# PCB.net
KiCad netlist of a schematic drawn in EasyEDA Pro
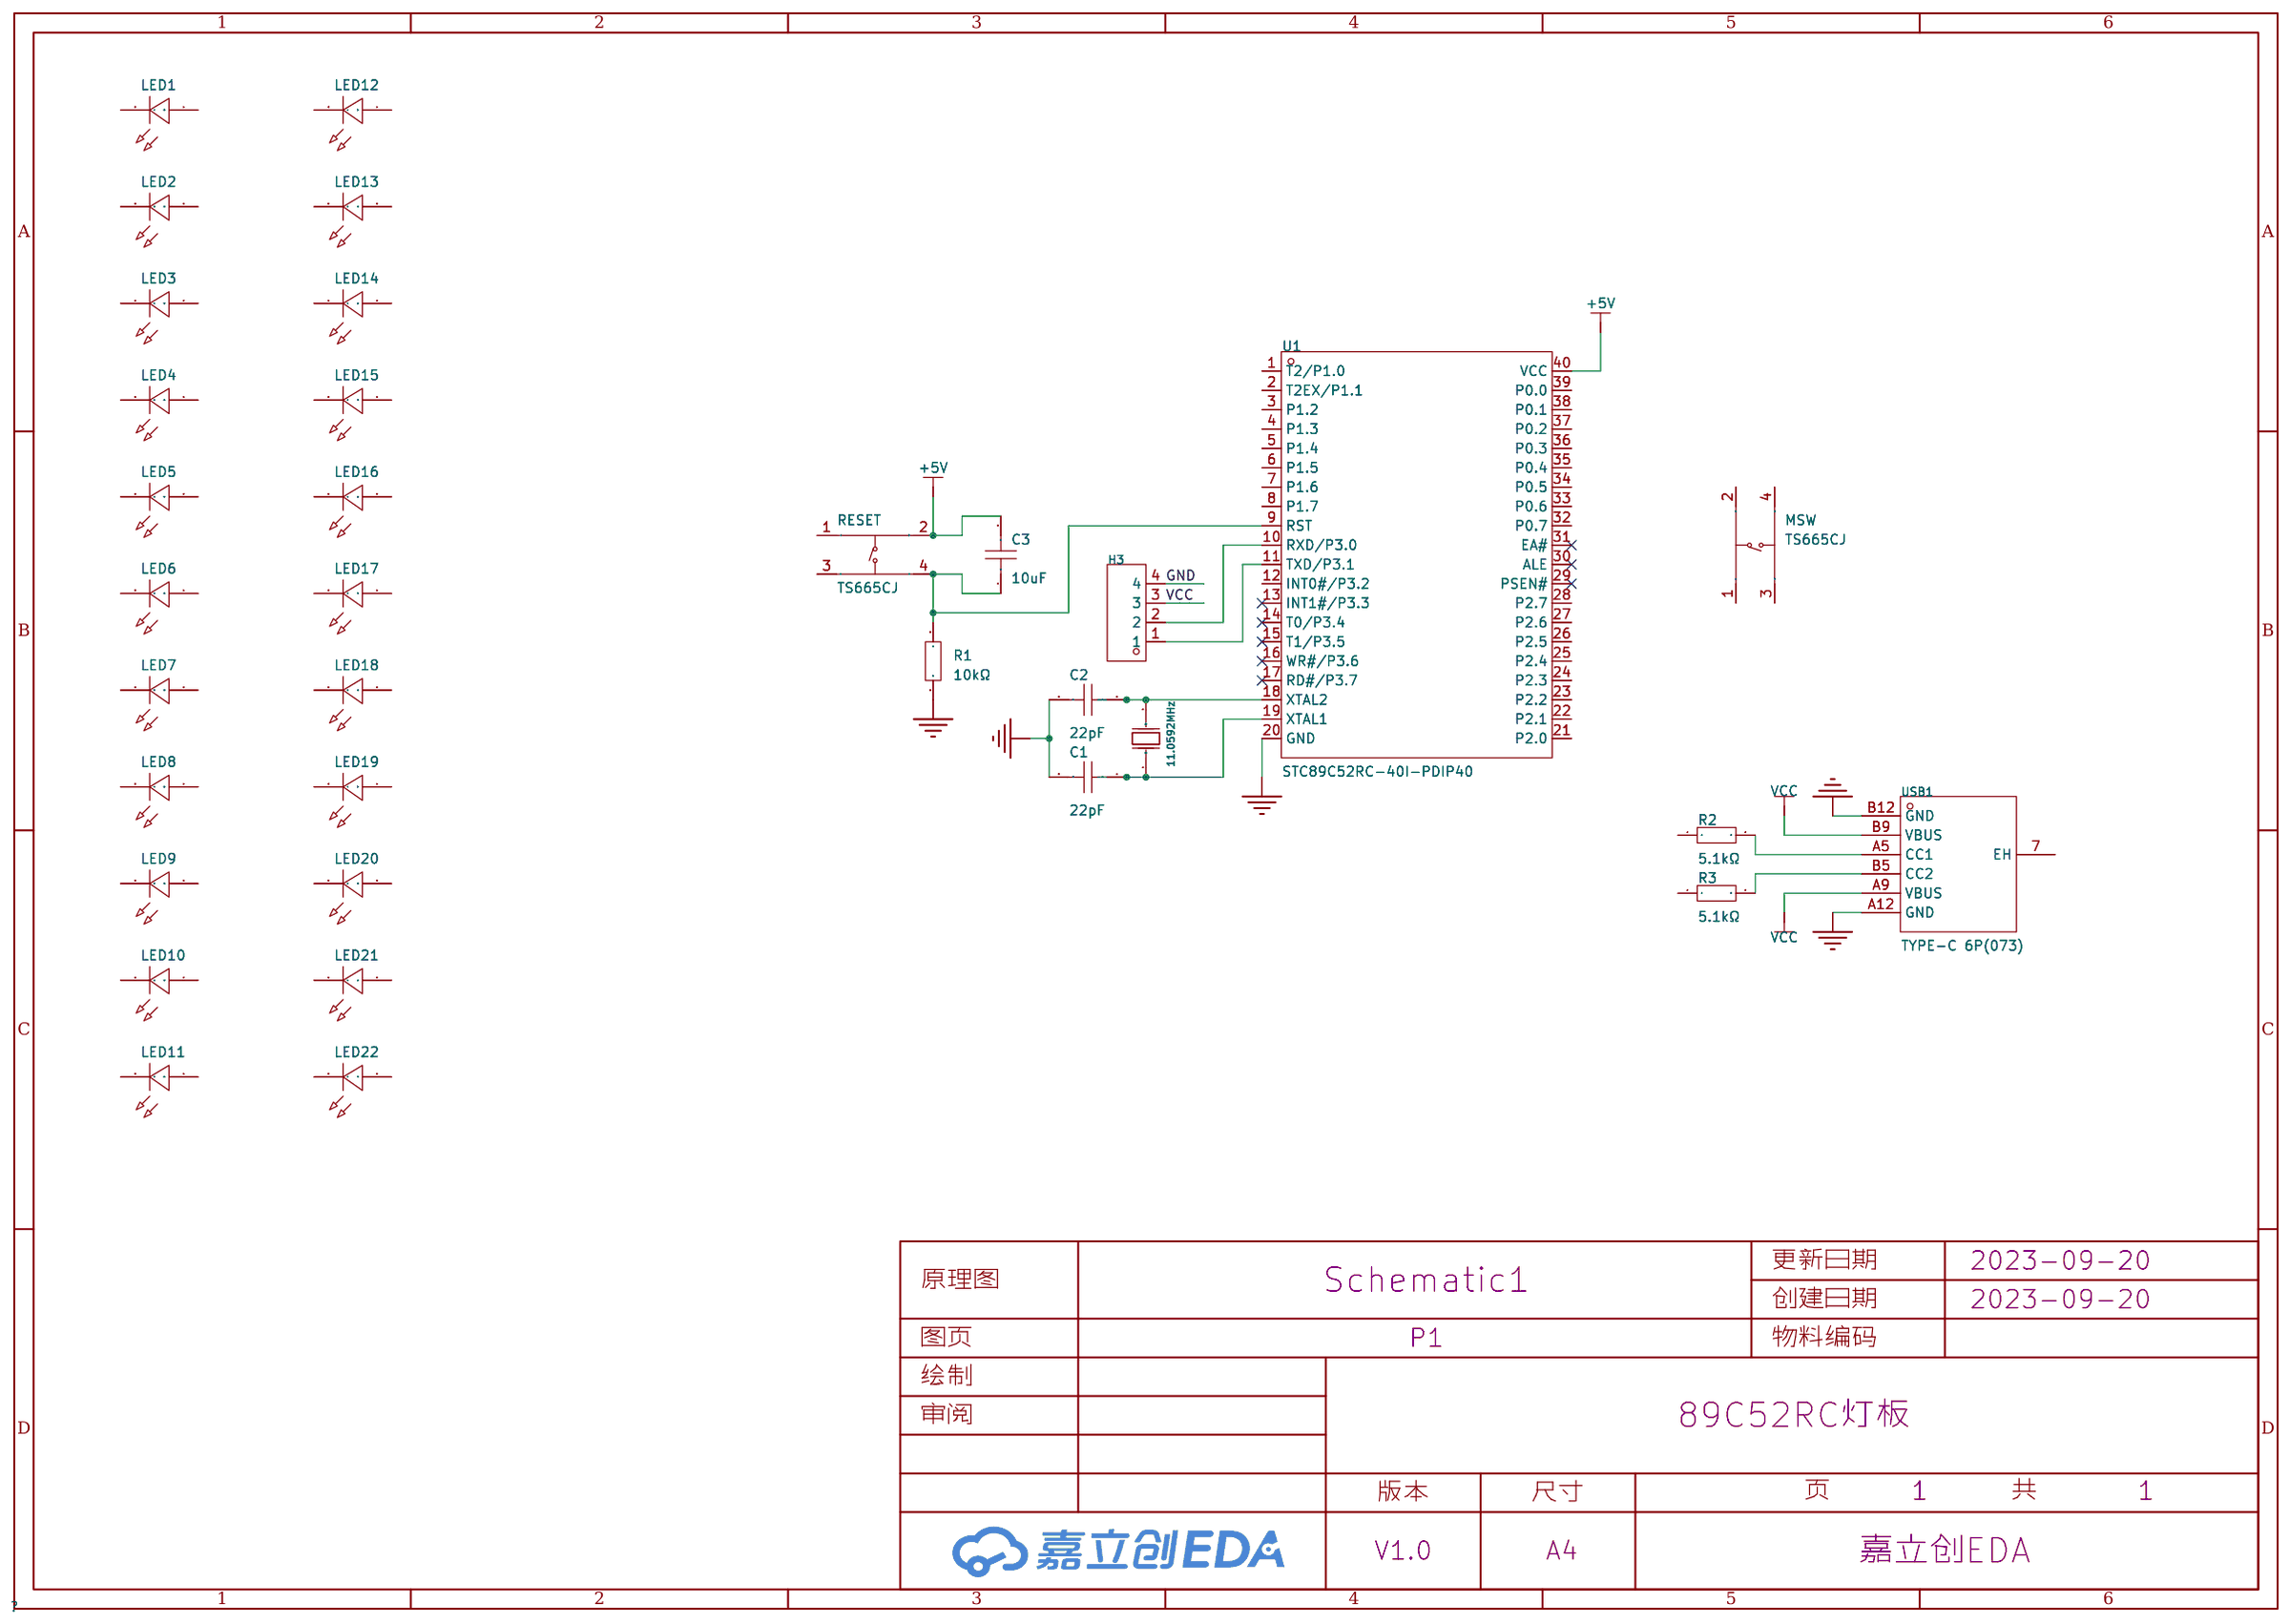
[diagram p0: schematic sheet]

(export (version "E")
  (design (tool "Eeschema 10.0.6"))
  (components
    (comp (ref "C1")
      (value "22pF")
      (footprint "easyedapro:C0603")
      (description "温度系数:C0G;精度:±5%;额定电压:50V;容值:22pF;")
      (fields (field (name "Manufacturer Part") "0603CG220J500NT") (field (name "Manufacturer") "FH(风华)"))
      (libsource (lib "easyedapro") (part "0603CG220J500NT"))
    )
    (comp (ref "C2")
      (value "22pF")
      (footprint "easyedapro:C0603")
      (description "温度系数:C0G;精度:±5%;额定电压:50V;容值:22pF;")
      (fields (field (name "Manufacturer Part") "0603CG220J500NT") (field (name "Manufacturer") "FH(风华)"))
      (libsource (lib "easyedapro") (part "0603CG220J500NT"))
    )
    (comp (ref "C3")
      (value "10uF")
      (footprint "easyedapro:C0603")
      (description "容值:10uF;精度:±10%;额定电压:10V;材质(温度系数):X5R;")
      (fields
        (field (name "Manufacturer Part") "CL10A106KP8NNNC")
        (field (name "Manufacturer") "SAMSUNG(三星)")
      )
      (libsource (lib "easyedapro") (part "CL10A106KP8NNNC"))
    )
    (comp (ref "H3")
      (value "PZ254V-11-04P")
      (footprint "easyedapro:HDR-TH_4P-P2.54-V-M")
      (fields (field (name "Manufacturer") "XFCN(兴飞)"))
      (libsource (lib "easyedapro") (part "PZ254V-11-04P_C2691448"))
    )
    (comp (ref "LED1")
      (value "~")
      (footprint "easyedapro:LED_TH-_5mm")
      (libsource (lib "easyedapro") (part "LED_TH-G"))
    )
    (comp (ref "LED2")
      (value "~")
      (footprint "easyedapro:LED_TH-_5mm")
      (libsource (lib "easyedapro") (part "LED_TH-G"))
    )
    (comp (ref "LED3")
      (value "~")
      (footprint "easyedapro:LED_TH-_5mm")
      (libsource (lib "easyedapro") (part "LED_TH-G"))
    )
    (comp (ref "LED4")
      (value "~")
      (footprint "easyedapro:LED_TH-_5mm")
      (libsource (lib "easyedapro") (part "LED_TH-G"))
    )
    (comp (ref "LED5")
      (value "~")
      (footprint "easyedapro:LED_TH-_5mm")
      (libsource (lib "easyedapro") (part "LED_TH-G"))
    )
    (comp (ref "LED6")
      (value "~")
      (footprint "easyedapro:LED_TH-_5mm")
      (libsource (lib "easyedapro") (part "LED_TH-G"))
    )
    (comp (ref "LED7")
      (value "~")
      (footprint "easyedapro:LED_TH-_5mm")
      (libsource (lib "easyedapro") (part "LED_TH-G"))
    )
    (comp (ref "LED8")
      (value "~")
      (footprint "easyedapro:LED_TH-_5mm")
      (libsource (lib "easyedapro") (part "LED_TH-G"))
    )
    (comp (ref "LED9")
      (value "~")
      (footprint "easyedapro:LED_TH-_5mm")
      (libsource (lib "easyedapro") (part "LED_TH-G"))
    )
    (comp (ref "LED10")
      (value "~")
      (footprint "easyedapro:LED_TH-_5mm")
      (libsource (lib "easyedapro") (part "LED_TH-G"))
    )
    (comp (ref "LED11")
      (value "~")
      (footprint "easyedapro:LED_TH-_5mm")
      (libsource (lib "easyedapro") (part "LED_TH-G"))
    )
    (comp (ref "LED12")
      (value "~")
      (footprint "easyedapro:LED_TH-_5mm")
      (libsource (lib "easyedapro") (part "LED_TH-G"))
    )
    (comp (ref "LED13")
      (value "~")
      (footprint "easyedapro:LED_TH-_5mm")
      (libsource (lib "easyedapro") (part "LED_TH-G"))
    )
    (comp (ref "LED14")
      (value "~")
      (footprint "easyedapro:LED_TH-_5mm")
      (libsource (lib "easyedapro") (part "LED_TH-G"))
    )
    (comp (ref "LED15")
      (value "~")
      (footprint "easyedapro:LED_TH-_5mm")
      (libsource (lib "easyedapro") (part "LED_TH-G"))
    )
    (comp (ref "LED16")
      (value "~")
      (footprint "easyedapro:LED_TH-_5mm")
      (libsource (lib "easyedapro") (part "LED_TH-G"))
    )
    (comp (ref "LED17")
      (value "~")
      (footprint "easyedapro:LED_TH-_5mm")
      (libsource (lib "easyedapro") (part "LED_TH-G"))
    )
    (comp (ref "LED18")
      (value "~")
      (footprint "easyedapro:LED_TH-_5mm")
      (libsource (lib "easyedapro") (part "LED_TH-G"))
    )
    (comp (ref "LED19")
      (value "~")
      (footprint "easyedapro:LED_TH-_5mm")
      (libsource (lib "easyedapro") (part "LED_TH-G"))
    )
    (comp (ref "LED20")
      (value "~")
      (footprint "easyedapro:LED_TH-_5mm")
      (libsource (lib "easyedapro") (part "LED_TH-G"))
    )
    (comp (ref "LED21")
      (value "~")
      (footprint "easyedapro:LED_TH-_5mm")
      (libsource (lib "easyedapro") (part "LED_TH-G"))
    )
    (comp (ref "LED22")
      (value "~")
      (footprint "easyedapro:LED_TH-_5mm")
      (libsource (lib "easyedapro") (part "LED_TH-G"))
    )
    (comp (ref "MSW")
      (value "TS665CJ")
      (footprint "easyedapro:SW-TH_4P-L6.0-W6.0-P4.50-LS6.5")
      (description "触点电流:50mA;额定电压(DC):12V;电路结构:单刀单掷;安装方式:直插;带灯:-;机械寿命:-;")
      (fields (field (name "Manufacturer") "SHOU HAN(首韩)"))
      (libsource (lib "easyedapro") (part "TS665CJ"))
    )
    (comp (ref "R1")
      (value "10kΩ")
      (footprint "easyedapro:R0603")
      (description "电阻类型:厚膜电阻;阻值:10kΩ;精度:±1%;功率:100mW;")
      (fields
        (field (name "Manufacturer Part") "0603WAF1002T5E")
        (field (name "Manufacturer") "UNI-ROYAL(厚声)")
      )
      (libsource (lib "easyedapro") (part "0603WAF1002T5E"))
    )
    (comp (ref "R2")
      (value "5.1kΩ")
      (footprint "easyedapro:R0603")
      (description "电阻类型:厚膜电阻;阻值:5.1kΩ;精度:±1%;功率:100mW;")
      (fields
        (field (name "Manufacturer Part") "0603WAF5101T5E")
        (field (name "Manufacturer") "UNI-ROYAL(厚声)")
      )
      (libsource (lib "easyedapro") (part "0603WAF5101T5E"))
    )
    (comp (ref "R3")
      (value "5.1kΩ")
      (footprint "easyedapro:R0603")
      (description "电阻类型:厚膜电阻;阻值:5.1kΩ;精度:±1%;功率:100mW;")
      (fields
        (field (name "Manufacturer Part") "0603WAF5101T5E")
        (field (name "Manufacturer") "UNI-ROYAL(厚声)")
      )
      (libsource (lib "easyedapro") (part "0603WAF5101T5E"))
    )
    (comp (ref "RESET")
      (value "TS665CJ")
      (footprint "easyedapro:SW-TH_4P-L6.0-W6.0-P4.50-LS6.5")
      (description "触点电流:50mA;额定电压(DC):12V;电路结构:单刀单掷;安装方式:直插;带灯:-;机械寿命:-;")
      (fields (field (name "Manufacturer") "SHOU HAN(首韩)"))
      (libsource (lib "easyedapro") (part "TS665CJ"))
    )
    (comp (ref "U1")
      (value "STC89C52RC-40I-PDIP40")
      (footprint "easyedapro:DIP-40_L52.0-W13.7-P2.54-LS15.2-BL")
      (fields (field (name "Manufacturer") "STC(宏晶)"))
      (libsource (lib "easyedapro") (part "STC89C52RC-40I"))
    )
    (comp (ref "USB1")
      (value "TYPE-C 6P(073)")
      (footprint "easyedapro:TYPE-C-SMD_TYPE-C-6P")
      (description "连接器类型:Type-C;标准:-;公母:母座;触点数量:6P;端口数量:1;安装方式:卧贴;额定电流 - 电源:5A;工作温度范围:-25°C~+85°C;")
      (fields (field (name "Manufacturer") "SHOU HAN(首韩)"))
      (libsource (lib "easyedapro") (part "TYPE-C 6P(073)"))
    )
    (comp (ref "X1")
      (value "11.0592MHz")
      (footprint "easyedapro:HC-49US_L11.5-W4.5-P4.88")
      (description "频率:11.0592MHz;频率公差:±20ppm;负载电容:20pF;")
      (fields
        (field (name "Manufacturer Part") "X49SD110592MSD2SC")
        (field (name "Manufacturer") "YXC(扬兴晶振)")
      )
      (libsource (lib "easyedapro") (part "X49SD110592MSD2SC"))
    )
  )
  (nets
    (net (code "1") (name "+5V") (class "Default")
      (node (ref "C3") (pin "2") (pinfunction "2_2") (pintype "input"))
      (node (ref "RESET") (pin "2") (pinfunction "B_2") (pintype "input"))
      (node (ref "U1") (pin "40") (pinfunction "VCC_40") (pintype "input"))
    )
    (net (code "2") (name "GND") (class "Default")
      (node (ref "C1") (pin "2") (pinfunction "2_2") (pintype "input"))
      (node (ref "C2") (pin "2") (pinfunction "2_2") (pintype "input"))
      (node (ref "H3") (pin "4") (pinfunction "4_4") (pintype "input"))
      (node (ref "R1") (pin "1") (pinfunction "1_1") (pintype "input"))
      (node (ref "U1") (pin "20") (pinfunction "GND_20") (pintype "input"))
      (node (ref "USB1") (pin "A12") (pinfunction "GND_A12") (pintype "input"))
      (node (ref "USB1") (pin "B12") (pinfunction "GND_B12") (pintype "input"))
    )
    (net (code "3") (name "Net-(RESET-D)") (class "Default")
      (node (ref "C3") (pin "1") (pinfunction "1_1") (pintype "input"))
      (node (ref "R1") (pin "2") (pinfunction "2_2") (pintype "input"))
      (node (ref "RESET") (pin "4") (pinfunction "D_4") (pintype "input"))
      (node (ref "U1") (pin "9") (pinfunction "RST_9") (pintype "input"))
    )
    (net (code "4") (name "Net-(U1-RXD{slash}P3.0)") (class "Default")
      (node (ref "H3") (pin "2") (pinfunction "2_2") (pintype "input"))
      (node (ref "U1") (pin "10") (pinfunction "RXD/P3.0_10") (pintype "input"))
    )
    (net (code "5") (name "Net-(U1-TXD{slash}P3.1)") (class "Default")
      (node (ref "H3") (pin "1") (pinfunction "1_1") (pintype "input"))
      (node (ref "U1") (pin "11") (pinfunction "TXD/P3.1_11") (pintype "input"))
    )
    (net (code "6") (name "Net-(U1-XTAL1)") (class "Default")
      (node (ref "C1") (pin "1") (pinfunction "1_1") (pintype "input"))
      (node (ref "U1") (pin "19") (pinfunction "XTAL1_19") (pintype "input"))
      (node (ref "X1") (pin "1") (pinfunction "OSC1_1") (pintype "input"))
    )
    (net (code "7") (name "Net-(U1-XTAL2)") (class "Default")
      (node (ref "C2") (pin "1") (pinfunction "1_1") (pintype "input"))
      (node (ref "U1") (pin "18") (pinfunction "XTAL2_18") (pintype "input"))
      (node (ref "X1") (pin "2") (pinfunction "OSC2_2") (pintype "input"))
    )
    (net (code "8") (name "Net-(USB1-CC1)") (class "Default")
      (node (ref "R2") (pin "2") (pinfunction "2_2") (pintype "input"))
      (node (ref "USB1") (pin "A5") (pinfunction "CC1_A5") (pintype "input"))
    )
    (net (code "9") (name "Net-(USB1-CC2)") (class "Default")
      (node (ref "R3") (pin "2") (pinfunction "2_2") (pintype "input"))
      (node (ref "USB1") (pin "B5") (pinfunction "CC2_B5") (pintype "input"))
    )
    (net (code "10") (name "VCC") (class "Default")
      (node (ref "H3") (pin "3") (pinfunction "3_3") (pintype "input"))
      (node (ref "USB1") (pin "A9") (pinfunction "VBUS_A9") (pintype "input"))
      (node (ref "USB1") (pin "B9") (pinfunction "VBUS_B9") (pintype "input"))
    )
    (net (code "11") (name "unconnected-(LED1-A-Pad2)") (class "Default")
      (node (ref "LED1") (pin "2") (pinfunction "A_2") (pintype "input"))
    )
    (net (code "12") (name "unconnected-(LED1-C-Pad1)") (class "Default")
      (node (ref "LED1") (pin "1") (pinfunction "C_1") (pintype "input"))
    )
    (net (code "13") (name "unconnected-(LED2-A-Pad2)") (class "Default")
      (node (ref "LED2") (pin "2") (pinfunction "A_2") (pintype "input"))
    )
    (net (code "14") (name "unconnected-(LED2-C-Pad1)") (class "Default")
      (node (ref "LED2") (pin "1") (pinfunction "C_1") (pintype "input"))
    )
    (net (code "15") (name "unconnected-(LED3-A-Pad2)") (class "Default")
      (node (ref "LED3") (pin "2") (pinfunction "A_2") (pintype "input"))
    )
    (net (code "16") (name "unconnected-(LED3-C-Pad1)") (class "Default")
      (node (ref "LED3") (pin "1") (pinfunction "C_1") (pintype "input"))
    )
    (net (code "17") (name "unconnected-(LED4-A-Pad2)") (class "Default")
      (node (ref "LED4") (pin "2") (pinfunction "A_2") (pintype "input"))
    )
    (net (code "18") (name "unconnected-(LED4-C-Pad1)") (class "Default")
      (node (ref "LED4") (pin "1") (pinfunction "C_1") (pintype "input"))
    )
    (net (code "19") (name "unconnected-(LED5-A-Pad2)") (class "Default")
      (node (ref "LED5") (pin "2") (pinfunction "A_2") (pintype "input"))
    )
    (net (code "20") (name "unconnected-(LED5-C-Pad1)") (class "Default")
      (node (ref "LED5") (pin "1") (pinfunction "C_1") (pintype "input"))
    )
    (net (code "21") (name "unconnected-(LED6-A-Pad2)") (class "Default")
      (node (ref "LED6") (pin "2") (pinfunction "A_2") (pintype "input"))
    )
    (net (code "22") (name "unconnected-(LED6-C-Pad1)") (class "Default")
      (node (ref "LED6") (pin "1") (pinfunction "C_1") (pintype "input"))
    )
    (net (code "23") (name "unconnected-(LED7-A-Pad2)") (class "Default")
      (node (ref "LED7") (pin "2") (pinfunction "A_2") (pintype "input"))
    )
    (net (code "24") (name "unconnected-(LED7-C-Pad1)") (class "Default")
      (node (ref "LED7") (pin "1") (pinfunction "C_1") (pintype "input"))
    )
    (net (code "25") (name "unconnected-(LED8-A-Pad2)") (class "Default")
      (node (ref "LED8") (pin "2") (pinfunction "A_2") (pintype "input"))
    )
    (net (code "26") (name "unconnected-(LED8-C-Pad1)") (class "Default")
      (node (ref "LED8") (pin "1") (pinfunction "C_1") (pintype "input"))
    )
    (net (code "27") (name "unconnected-(LED9-A-Pad2)") (class "Default")
      (node (ref "LED9") (pin "2") (pinfunction "A_2") (pintype "input"))
    )
    (net (code "28") (name "unconnected-(LED9-C-Pad1)") (class "Default")
      (node (ref "LED9") (pin "1") (pinfunction "C_1") (pintype "input"))
    )
    (net (code "29") (name "unconnected-(LED10-A-Pad2)") (class "Default")
      (node (ref "LED10") (pin "2") (pinfunction "A_2") (pintype "input"))
    )
    (net (code "30") (name "unconnected-(LED10-C-Pad1)") (class "Default")
      (node (ref "LED10") (pin "1") (pinfunction "C_1") (pintype "input"))
    )
    (net (code "31") (name "unconnected-(LED11-A-Pad2)") (class "Default")
      (node (ref "LED11") (pin "2") (pinfunction "A_2") (pintype "input"))
    )
    (net (code "32") (name "unconnected-(LED11-C-Pad1)") (class "Default")
      (node (ref "LED11") (pin "1") (pinfunction "C_1") (pintype "input"))
    )
    (net (code "33") (name "unconnected-(LED12-A-Pad2)") (class "Default")
      (node (ref "LED12") (pin "2") (pinfunction "A_2") (pintype "input"))
    )
    (net (code "34") (name "unconnected-(LED12-C-Pad1)") (class "Default")
      (node (ref "LED12") (pin "1") (pinfunction "C_1") (pintype "input"))
    )
    (net (code "35") (name "unconnected-(LED13-A-Pad2)") (class "Default")
      (node (ref "LED13") (pin "2") (pinfunction "A_2") (pintype "input"))
    )
    (net (code "36") (name "unconnected-(LED13-C-Pad1)") (class "Default")
      (node (ref "LED13") (pin "1") (pinfunction "C_1") (pintype "input"))
    )
    (net (code "37") (name "unconnected-(LED14-A-Pad2)") (class "Default")
      (node (ref "LED14") (pin "2") (pinfunction "A_2") (pintype "input"))
    )
    (net (code "38") (name "unconnected-(LED14-C-Pad1)") (class "Default")
      (node (ref "LED14") (pin "1") (pinfunction "C_1") (pintype "input"))
    )
    (net (code "39") (name "unconnected-(LED15-A-Pad2)") (class "Default")
      (node (ref "LED15") (pin "2") (pinfunction "A_2") (pintype "input"))
    )
    (net (code "40") (name "unconnected-(LED15-C-Pad1)") (class "Default")
      (node (ref "LED15") (pin "1") (pinfunction "C_1") (pintype "input"))
    )
    (net (code "41") (name "unconnected-(LED16-A-Pad2)") (class "Default")
      (node (ref "LED16") (pin "2") (pinfunction "A_2") (pintype "input"))
    )
    (net (code "42") (name "unconnected-(LED16-C-Pad1)") (class "Default")
      (node (ref "LED16") (pin "1") (pinfunction "C_1") (pintype "input"))
    )
    (net (code "43") (name "unconnected-(LED17-A-Pad2)") (class "Default")
      (node (ref "LED17") (pin "2") (pinfunction "A_2") (pintype "input"))
    )
    (net (code "44") (name "unconnected-(LED17-C-Pad1)") (class "Default")
      (node (ref "LED17") (pin "1") (pinfunction "C_1") (pintype "input"))
    )
    (net (code "45") (name "unconnected-(LED18-A-Pad2)") (class "Default")
      (node (ref "LED18") (pin "2") (pinfunction "A_2") (pintype "input"))
    )
    (net (code "46") (name "unconnected-(LED18-C-Pad1)") (class "Default")
      (node (ref "LED18") (pin "1") (pinfunction "C_1") (pintype "input"))
    )
    (net (code "47") (name "unconnected-(LED19-A-Pad2)") (class "Default")
      (node (ref "LED19") (pin "2") (pinfunction "A_2") (pintype "input"))
    )
    (net (code "48") (name "unconnected-(LED19-C-Pad1)") (class "Default")
      (node (ref "LED19") (pin "1") (pinfunction "C_1") (pintype "input"))
    )
    (net (code "49") (name "unconnected-(LED20-A-Pad2)") (class "Default")
      (node (ref "LED20") (pin "2") (pinfunction "A_2") (pintype "input"))
    )
    (net (code "50") (name "unconnected-(LED20-C-Pad1)") (class "Default")
      (node (ref "LED20") (pin "1") (pinfunction "C_1") (pintype "input"))
    )
    (net (code "51") (name "unconnected-(LED21-A-Pad2)") (class "Default")
      (node (ref "LED21") (pin "2") (pinfunction "A_2") (pintype "input"))
    )
    (net (code "52") (name "unconnected-(LED21-C-Pad1)") (class "Default")
      (node (ref "LED21") (pin "1") (pinfunction "C_1") (pintype "input"))
    )
    (net (code "53") (name "unconnected-(LED22-A-Pad2)") (class "Default")
      (node (ref "LED22") (pin "2") (pinfunction "A_2") (pintype "input"))
    )
    (net (code "54") (name "unconnected-(LED22-C-Pad1)") (class "Default")
      (node (ref "LED22") (pin "1") (pinfunction "C_1") (pintype "input"))
    )
    (net (code "55") (name "unconnected-(MSW-A-Pad1)") (class "Default")
      (node (ref "MSW") (pin "1") (pinfunction "A_1") (pintype "input"))
    )
    (net (code "56") (name "unconnected-(MSW-B-Pad2)") (class "Default")
      (node (ref "MSW") (pin "2") (pinfunction "B_2") (pintype "input"))
    )
    (net (code "57") (name "unconnected-(MSW-C-Pad3)") (class "Default")
      (node (ref "MSW") (pin "3") (pinfunction "C_3") (pintype "input"))
    )
    (net (code "58") (name "unconnected-(MSW-D-Pad4)") (class "Default")
      (node (ref "MSW") (pin "4") (pinfunction "D_4") (pintype "input"))
    )
    (net (code "59") (name "unconnected-(R2-Pad1)") (class "Default")
      (node (ref "R2") (pin "1") (pinfunction "1_1") (pintype "input"))
    )
    (net (code "60") (name "unconnected-(R3-Pad1)") (class "Default")
      (node (ref "R3") (pin "1") (pinfunction "1_1") (pintype "input"))
    )
    (net (code "61") (name "unconnected-(RESET-A-Pad1)") (class "Default")
      (node (ref "RESET") (pin "1") (pinfunction "A_1") (pintype "input"))
    )
    (net (code "62") (name "unconnected-(RESET-C-Pad3)") (class "Default")
      (node (ref "RESET") (pin "3") (pinfunction "C_3") (pintype "input"))
    )
    (net (code "63") (name "unconnected-(U1-ALE-Pad30)") (class "Default")
      (node (ref "U1") (pin "30") (pinfunction "ALE_30") (pintype "input+no_connect"))
    )
    (net (code "64") (name "unconnected-(U1-EA#-Pad31)") (class "Default")
      (node (ref "U1") (pin "31") (pinfunction "EA#_31") (pintype "input+no_connect"))
    )
    (net (code "65") (name "unconnected-(U1-INT0#{slash}P3.2-Pad12)") (class "Default")
      (node (ref "U1") (pin "12") (pinfunction "INT0#/P3.2_12") (pintype "input"))
    )
    (net (code "66") (name "unconnected-(U1-INT1#{slash}P3.3-Pad13)") (class "Default")
      (node (ref "U1") (pin "13") (pinfunction "INT1#/P3.3_13") (pintype "input+no_connect"))
    )
    (net (code "67") (name "unconnected-(U1-P0.0-Pad39)") (class "Default")
      (node (ref "U1") (pin "39") (pinfunction "P0.0_39") (pintype "input"))
    )
    (net (code "68") (name "unconnected-(U1-P0.1-Pad38)") (class "Default")
      (node (ref "U1") (pin "38") (pinfunction "P0.1_38") (pintype "input"))
    )
    (net (code "69") (name "unconnected-(U1-P0.2-Pad37)") (class "Default")
      (node (ref "U1") (pin "37") (pinfunction "P0.2_37") (pintype "input"))
    )
    (net (code "70") (name "unconnected-(U1-P0.3-Pad36)") (class "Default")
      (node (ref "U1") (pin "36") (pinfunction "P0.3_36") (pintype "input"))
    )
    (net (code "71") (name "unconnected-(U1-P0.4-Pad35)") (class "Default")
      (node (ref "U1") (pin "35") (pinfunction "P0.4_35") (pintype "input"))
    )
    (net (code "72") (name "unconnected-(U1-P0.5-Pad34)") (class "Default")
      (node (ref "U1") (pin "34") (pinfunction "P0.5_34") (pintype "input"))
    )
    (net (code "73") (name "unconnected-(U1-P0.6-Pad33)") (class "Default")
      (node (ref "U1") (pin "33") (pinfunction "P0.6_33") (pintype "input"))
    )
    (net (code "74") (name "unconnected-(U1-P0.7-Pad32)") (class "Default")
      (node (ref "U1") (pin "32") (pinfunction "P0.7_32") (pintype "input"))
    )
    (net (code "75") (name "unconnected-(U1-P1.2-Pad3)") (class "Default")
      (node (ref "U1") (pin "3") (pinfunction "P1.2_3") (pintype "input"))
    )
    (net (code "76") (name "unconnected-(U1-P1.3-Pad4)") (class "Default")
      (node (ref "U1") (pin "4") (pinfunction "P1.3_4") (pintype "input"))
    )
    (net (code "77") (name "unconnected-(U1-P1.4-Pad5)") (class "Default")
      (node (ref "U1") (pin "5") (pinfunction "P1.4_5") (pintype "input"))
    )
    (net (code "78") (name "unconnected-(U1-P1.5-Pad6)") (class "Default")
      (node (ref "U1") (pin "6") (pinfunction "P1.5_6") (pintype "input"))
    )
    (net (code "79") (name "unconnected-(U1-P1.6-Pad7)") (class "Default")
      (node (ref "U1") (pin "7") (pinfunction "P1.6_7") (pintype "input"))
    )
    (net (code "80") (name "unconnected-(U1-P1.7-Pad8)") (class "Default")
      (node (ref "U1") (pin "8") (pinfunction "P1.7_8") (pintype "input"))
    )
    (net (code "81") (name "unconnected-(U1-P2.0-Pad21)") (class "Default")
      (node (ref "U1") (pin "21") (pinfunction "P2.0_21") (pintype "input"))
    )
    (net (code "82") (name "unconnected-(U1-P2.1-Pad22)") (class "Default")
      (node (ref "U1") (pin "22") (pinfunction "P2.1_22") (pintype "input"))
    )
    (net (code "83") (name "unconnected-(U1-P2.2-Pad23)") (class "Default")
      (node (ref "U1") (pin "23") (pinfunction "P2.2_23") (pintype "input"))
    )
    (net (code "84") (name "unconnected-(U1-P2.3-Pad24)") (class "Default")
      (node (ref "U1") (pin "24") (pinfunction "P2.3_24") (pintype "input"))
    )
    (net (code "85") (name "unconnected-(U1-P2.4-Pad25)") (class "Default")
      (node (ref "U1") (pin "25") (pinfunction "P2.4_25") (pintype "input"))
    )
    (net (code "86") (name "unconnected-(U1-P2.5-Pad26)") (class "Default")
      (node (ref "U1") (pin "26") (pinfunction "P2.5_26") (pintype "input"))
    )
    (net (code "87") (name "unconnected-(U1-P2.6-Pad27)") (class "Default")
      (node (ref "U1") (pin "27") (pinfunction "P2.6_27") (pintype "input"))
    )
    (net (code "88") (name "unconnected-(U1-P2.7-Pad28)") (class "Default")
      (node (ref "U1") (pin "28") (pinfunction "P2.7_28") (pintype "input"))
    )
    (net (code "89") (name "unconnected-(U1-PSEN#-Pad29)") (class "Default")
      (node (ref "U1") (pin "29") (pinfunction "PSEN#_29") (pintype "input+no_connect"))
    )
    (net (code "90") (name "unconnected-(U1-RD#{slash}P3.7-Pad17)") (class "Default")
      (node (ref "U1") (pin "17") (pinfunction "RD#/P3.7_17") (pintype "input+no_connect"))
    )
    (net (code "91") (name "unconnected-(U1-T0{slash}P3.4-Pad14)") (class "Default")
      (node (ref "U1") (pin "14") (pinfunction "T0/P3.4_14") (pintype "input+no_connect"))
    )
    (net (code "92") (name "unconnected-(U1-T1{slash}P3.5-Pad15)") (class "Default")
      (node (ref "U1") (pin "15") (pinfunction "T1/P3.5_15") (pintype "input+no_connect"))
    )
    (net (code "93") (name "unconnected-(U1-T2EX{slash}P1.1-Pad2)") (class "Default")
      (node (ref "U1") (pin "2") (pinfunction "T2EX/P1.1_2") (pintype "input"))
    )
    (net (code "94") (name "unconnected-(U1-T2{slash}P1.0-Pad1)") (class "Default")
      (node (ref "U1") (pin "1") (pinfunction "T2/P1.0_1") (pintype "input"))
    )
    (net (code "95") (name "unconnected-(U1-WR#{slash}P3.6-Pad16)") (class "Default")
      (node (ref "U1") (pin "16") (pinfunction "WR#/P3.6_16") (pintype "input+no_connect"))
    )
    (net (code "96") (name "unconnected-(USB1-EH-Pad7)") (class "Default")
      (node (ref "USB1") (pin "7") (pinfunction "EH_7") (pintype "input"))
    )
  )
)
